# linesensor.net
KiCad netlist of a schematic drawn in EAGLE
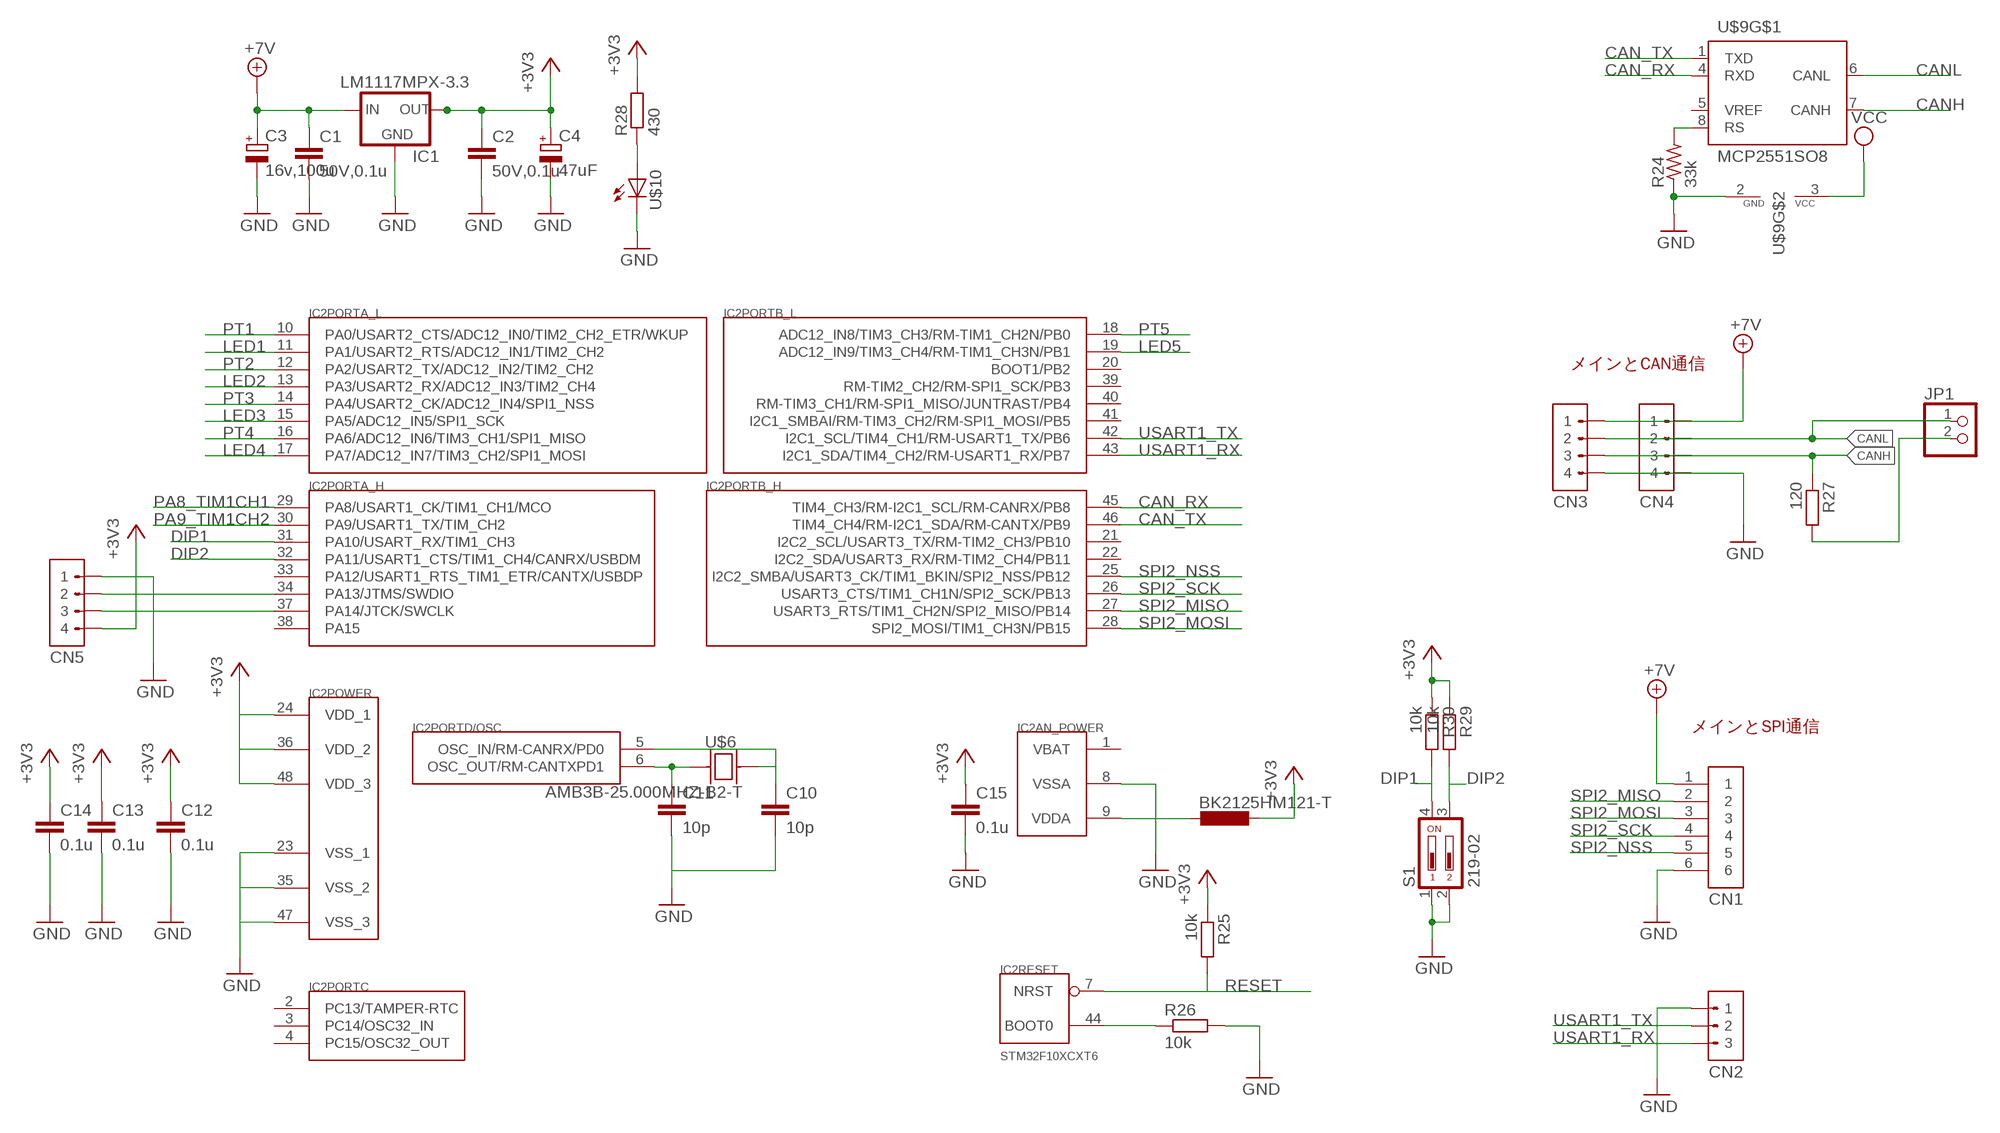
[diagram p0: schematic, sheet 1, part 1 of 2]
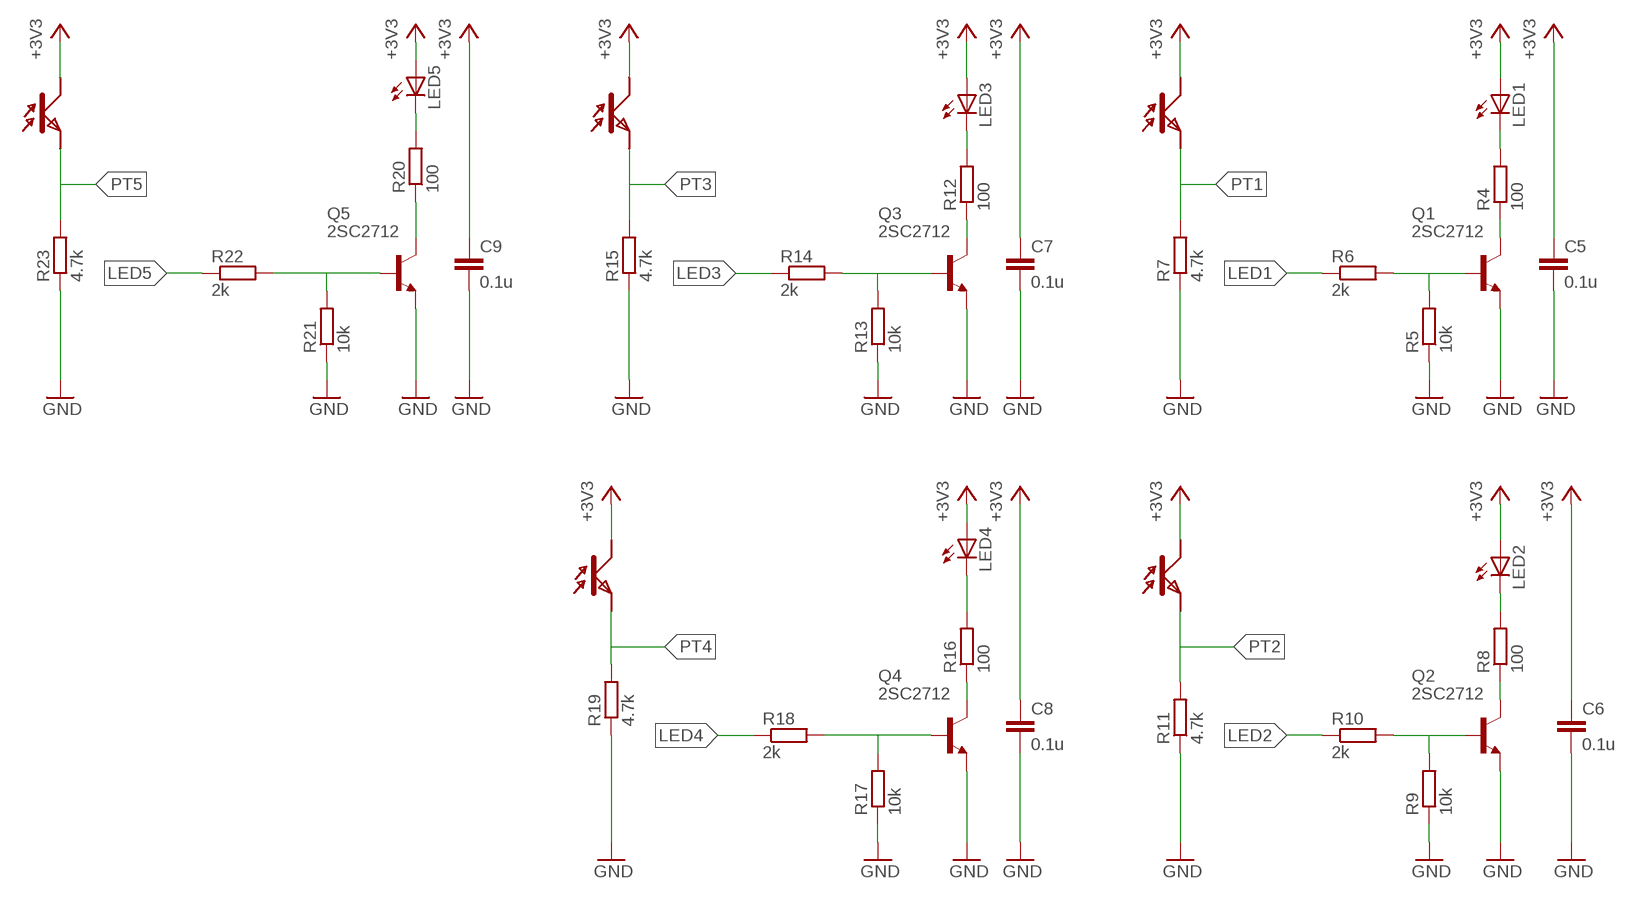
[diagram p1: schematic, sheet 1, part 2 of 2]

(export (version "E")
  (design (tool "Eeschema 10.0.6"))
  (components
    (comp (ref "BK2125HM121-T")
      (value "L-EUL2012C")
      (footprint "eagle-import:L2012C")
      (libsource (lib "eagle-import") (part "L-EUL2012C"))
    )
    (comp (ref "C1")
      (value "50V,0.1u")
      (footprint "eagle-import:C0603K")
      (libsource (lib "eagle-import") (part "C-EUC0603K"))
    )
    (comp (ref "C2")
      (value "50V,0.1u")
      (footprint "eagle-import:C0603K")
      (libsource (lib "eagle-import") (part "C-EUC0603K"))
    )
    (comp (ref "C3")
      (value "16v,100u")
      (footprint "eagle-import:153CLV-0605")
      (libsource (lib "eagle-import") (part "CPOL-EU153CLV-0605"))
    )
    (comp (ref "C4")
      (value "47uF")
      (footprint "eagle-import:153CLV-0405")
      (libsource (lib "eagle-import") (part "CPOL-EU153CLV-0405"))
    )
    (comp (ref "C5")
      (value "0.1u")
      (footprint "eagle-import:C0603K")
      (libsource (lib "eagle-import") (part "C-EUC0603K"))
    )
    (comp (ref "C6")
      (value "0.1u")
      (footprint "eagle-import:C0603K")
      (libsource (lib "eagle-import") (part "C-EUC0603K"))
    )
    (comp (ref "C7")
      (value "0.1u")
      (footprint "eagle-import:C0603K")
      (libsource (lib "eagle-import") (part "C-EUC0603K"))
    )
    (comp (ref "C8")
      (value "0.1u")
      (footprint "eagle-import:C0603K")
      (libsource (lib "eagle-import") (part "C-EUC0603K"))
    )
    (comp (ref "C9")
      (value "0.1u")
      (footprint "eagle-import:C0603K")
      (libsource (lib "eagle-import") (part "C-EUC0603K"))
    )
    (comp (ref "C10")
      (value "10p")
      (footprint "eagle-import:C0603K")
      (libsource (lib "eagle-import") (part "C-EUC0603K"))
    )
    (comp (ref "C11")
      (value "10p")
      (footprint "eagle-import:C0603K")
      (libsource (lib "eagle-import") (part "C-EUC0603K"))
    )
    (comp (ref "C12")
      (value "0.1u")
      (footprint "eagle-import:C0603K")
      (libsource (lib "eagle-import") (part "C-EUC0603K"))
    )
    (comp (ref "C13")
      (value "0.1u")
      (footprint "eagle-import:C0603K")
      (libsource (lib "eagle-import") (part "C-EUC0603K"))
    )
    (comp (ref "C14")
      (value "0.1u")
      (footprint "eagle-import:C0603K")
      (libsource (lib "eagle-import") (part "C-EUC0603K"))
    )
    (comp (ref "C15")
      (value "0.1u")
      (footprint "eagle-import:C0603K")
      (libsource (lib "eagle-import") (part "C-EUC0603K"))
    )
    (comp (ref "CN1")
      (value "CN6")
      (footprint "eagle-import:JST-B6B-XH-A")
      (libsource (lib "eagle-import") (part "CN6"))
    )
    (comp (ref "CN2")
      (value "TOP_TYPE_3PIN")
      (footprint "eagle-import:TOP_TYPE_3PIN")
      (libsource (lib "eagle-import") (part "TOP_TYPE_3PIN"))
    )
    (comp (ref "CN3")
      (value "CN4-JST-XH-TOP")
      (footprint "eagle-import:JST-B4B-XH-A")
      (libsource (lib "eagle-import") (part "CN4-JST-XH-TOP"))
    )
    (comp (ref "CN4")
      (value "CN4-JST-XH-TOP")
      (footprint "eagle-import:JST-B4B-XH-A")
      (libsource (lib "eagle-import") (part "CN4-JST-XH-TOP"))
    )
    (comp (ref "CN5")
      (value "TOP_TYPE_4PIN")
      (footprint "eagle-import:TOP_TYPE_4PIN")
      (libsource (lib "eagle-import") (part "TOP_TYPE_4PIN"))
    )
    (comp (ref "IC1")
      (value "LM1117MPX-3.3")
      (footprint "eagle-import:SOT223")
      (libsource (lib "eagle-import") (part "LM1117"))
    )
    (comp (ref "IC2")
      (value "STM32F10XCXT6")
      (footprint "eagle-import:TQFP48")
      (libsource (lib "eagle-import") (part "STM32F10XCXT6"))
    )
    (comp (ref "JP1")
      (value "PINHD-1X2")
      (footprint "eagle-import:1X02")
      (libsource (lib "eagle-import") (part "PINHD-1X2"))
    )
    (comp (ref "LED1")
      (value "LED3MM")
      (footprint "eagle-import:LED3MM")
      (libsource (lib "eagle-import") (part "LED3MM"))
    )
    (comp (ref "LED2")
      (value "LED3MM")
      (footprint "eagle-import:LED3MM")
      (libsource (lib "eagle-import") (part "LED3MM"))
    )
    (comp (ref "LED3")
      (value "LED3MM")
      (footprint "eagle-import:LED3MM")
      (libsource (lib "eagle-import") (part "LED3MM"))
    )
    (comp (ref "LED4")
      (value "LED3MM")
      (footprint "eagle-import:LED3MM")
      (libsource (lib "eagle-import") (part "LED3MM"))
    )
    (comp (ref "LED5")
      (value "LED3MM")
      (footprint "eagle-import:LED3MM")
      (libsource (lib "eagle-import") (part "LED3MM"))
    )
    (comp (ref "Q1")
      (value "2SC2712")
      (footprint "eagle-import:SC-59(TYPE1)")
      (libsource (lib "eagle-import") (part "2SC2712"))
    )
    (comp (ref "Q2")
      (value "2SC2712")
      (footprint "eagle-import:SC-59(TYPE1)")
      (libsource (lib "eagle-import") (part "2SC2712"))
    )
    (comp (ref "Q3")
      (value "2SC2712")
      (footprint "eagle-import:SC-59(TYPE1)")
      (libsource (lib "eagle-import") (part "2SC2712"))
    )
    (comp (ref "Q4")
      (value "2SC2712")
      (footprint "eagle-import:SC-59(TYPE1)")
      (libsource (lib "eagle-import") (part "2SC2712"))
    )
    (comp (ref "Q5")
      (value "2SC2712")
      (footprint "eagle-import:SC-59(TYPE1)")
      (libsource (lib "eagle-import") (part "2SC2712"))
    )
    (comp (ref "R4")
      (value "100")
      (footprint "eagle-import:R0603")
      (libsource (lib "eagle-import") (part "R-EU_R0603"))
    )
    (comp (ref "R5")
      (value "10k")
      (footprint "eagle-import:R0603")
      (libsource (lib "eagle-import") (part "R-EU_R0603"))
    )
    (comp (ref "R6")
      (value "2k")
      (footprint "eagle-import:R0603")
      (libsource (lib "eagle-import") (part "R-EU_R0603"))
    )
    (comp (ref "R7")
      (value "4.7k")
      (footprint "eagle-import:R0603")
      (libsource (lib "eagle-import") (part "R-EU_R0603"))
    )
    (comp (ref "R8")
      (value "100")
      (footprint "eagle-import:R0603")
      (libsource (lib "eagle-import") (part "R-EU_R0603"))
    )
    (comp (ref "R9")
      (value "10k")
      (footprint "eagle-import:R0603")
      (libsource (lib "eagle-import") (part "R-EU_R0603"))
    )
    (comp (ref "R10")
      (value "2k")
      (footprint "eagle-import:R0603")
      (libsource (lib "eagle-import") (part "R-EU_R0603"))
    )
    (comp (ref "R11")
      (value "4.7k")
      (footprint "eagle-import:R0603")
      (libsource (lib "eagle-import") (part "R-EU_R0603"))
    )
    (comp (ref "R12")
      (value "100")
      (footprint "eagle-import:R0603")
      (libsource (lib "eagle-import") (part "R-EU_R0603"))
    )
    (comp (ref "R13")
      (value "10k")
      (footprint "eagle-import:R0603")
      (libsource (lib "eagle-import") (part "R-EU_R0603"))
    )
    (comp (ref "R14")
      (value "2k")
      (footprint "eagle-import:R0603")
      (libsource (lib "eagle-import") (part "R-EU_R0603"))
    )
    (comp (ref "R15")
      (value "4.7k")
      (footprint "eagle-import:R0603")
      (libsource (lib "eagle-import") (part "R-EU_R0603"))
    )
    (comp (ref "R16")
      (value "100")
      (footprint "eagle-import:R0603")
      (libsource (lib "eagle-import") (part "R-EU_R0603"))
    )
    (comp (ref "R17")
      (value "10k")
      (footprint "eagle-import:R0603")
      (libsource (lib "eagle-import") (part "R-EU_R0603"))
    )
    (comp (ref "R18")
      (value "2k")
      (footprint "eagle-import:R0603")
      (libsource (lib "eagle-import") (part "R-EU_R0603"))
    )
    (comp (ref "R19")
      (value "4.7k")
      (footprint "eagle-import:R0603")
      (libsource (lib "eagle-import") (part "R-EU_R0603"))
    )
    (comp (ref "R20")
      (value "100")
      (footprint "eagle-import:R0603")
      (libsource (lib "eagle-import") (part "R-EU_R0603"))
    )
    (comp (ref "R21")
      (value "10k")
      (footprint "eagle-import:R0603")
      (libsource (lib "eagle-import") (part "R-EU_R0603"))
    )
    (comp (ref "R22")
      (value "2k")
      (footprint "eagle-import:R0603")
      (libsource (lib "eagle-import") (part "R-EU_R0603"))
    )
    (comp (ref "R23")
      (value "4.7k")
      (footprint "eagle-import:R0603")
      (libsource (lib "eagle-import") (part "R-EU_R0603"))
    )
    (comp (ref "R24")
      (value "33k")
      (footprint "eagle-import:R0603")
      (libsource (lib "eagle-import") (part "R-US_R0603"))
    )
    (comp (ref "R25")
      (value "10k")
      (footprint "eagle-import:R0603")
      (libsource (lib "eagle-import") (part "R-EU_R0603"))
    )
    (comp (ref "R26")
      (value "10k")
      (footprint "eagle-import:R0603")
      (libsource (lib "eagle-import") (part "R-EU_R0603"))
    )
    (comp (ref "R27")
      (value "120")
      (footprint "eagle-import:R0603")
      (libsource (lib "eagle-import") (part "R-EU_R0603"))
    )
    (comp (ref "R28")
      (value "430")
      (footprint "eagle-import:R0603")
      (libsource (lib "eagle-import") (part "R-EU_R0603"))
    )
    (comp (ref "R29")
      (value "10k")
      (footprint "eagle-import:R0603")
      (libsource (lib "eagle-import") (part "R-EU_R0603"))
    )
    (comp (ref "R30")
      (value "10k")
      (footprint "eagle-import:R0603")
      (libsource (lib "eagle-import") (part "R-EU_R0603"))
    )
    (comp (ref "S1")
      (value "219-02")
      (footprint "eagle-import:CTS-219-02")
      (libsource (lib "eagle-import") (part "219-02"))
    )
    (comp (ref "U$1")
      (value "SFH213")
      (footprint "eagle-import:SFH213")
      (libsource (lib "eagle-import") (part "SFH213"))
    )
    (comp (ref "U$2")
      (value "SFH213")
      (footprint "eagle-import:SFH213")
      (libsource (lib "eagle-import") (part "SFH213"))
    )
    (comp (ref "U$3")
      (value "SFH213")
      (footprint "eagle-import:SFH213")
      (libsource (lib "eagle-import") (part "SFH213"))
    )
    (comp (ref "U$4")
      (value "SFH213")
      (footprint "eagle-import:SFH213")
      (libsource (lib "eagle-import") (part "SFH213"))
    )
    (comp (ref "U$5")
      (value "SFH213")
      (footprint "eagle-import:SFH213")
      (libsource (lib "eagle-import") (part "SFH213"))
    )
    (comp (ref "U$6")
      (value "AMB3B-25.000MHZ-B2-T")
      (footprint "eagle-import:4LCC")
      (libsource (lib "eagle-import") (part "AMB3B-25.000MHZ-B2-T"))
    )
    (comp (ref "U$9")
      (value "MCP2551SO8")
      (footprint "eagle-import:SO08")
      (libsource (lib "eagle-import") (part "MCP2551SO8"))
    )
    (comp (ref "U$10")
      (value "0603")
      (footprint "eagle-import:0603")
      (libsource (lib "eagle-import") (part "0603"))
    )
  )
  (nets
    (net (code "1") (name "+3V3") (class "Default")
      (node (ref "BK2125HM121-T") (pin "1") (pinfunction "1_1") (pintype "passive"))
      (node (ref "C12") (pin "1") (pinfunction "1_1") (pintype "passive"))
      (node (ref "C13") (pin "1") (pinfunction "1_1") (pintype "passive"))
      (node (ref "C14") (pin "1") (pinfunction "1_1") (pintype "passive"))
      (node (ref "C15") (pin "1") (pinfunction "1_1") (pintype "passive"))
      (node (ref "C2") (pin "1") (pinfunction "1_1") (pintype "passive"))
      (node (ref "C4") (pin "+") (pinfunction "+_+") (pintype "passive"))
      (node (ref "C5") (pin "1") (pinfunction "1_1") (pintype "passive"))
      (node (ref "C6") (pin "1") (pinfunction "1_1") (pintype "passive"))
      (node (ref "C7") (pin "1") (pinfunction "1_1") (pintype "passive"))
      (node (ref "C8") (pin "1") (pinfunction "1_1") (pintype "passive"))
      (node (ref "C9") (pin "1") (pinfunction "1_1") (pintype "passive"))
      (node (ref "CN5") (pin "4") (pinfunction "4_4") (pintype "passive"))
      (node (ref "IC1") (pin "2") (pinfunction "OUT1_2") (pintype "passive"))
      (node (ref "IC1") (pin "4") (pinfunction "OUT_4") (pintype "passive"))
      (node (ref "IC2") (pin "24") (pinfunction "VDD_1_24") (pintype "power_in"))
      (node (ref "IC2") (pin "36") (pinfunction "VDD_2_36") (pintype "power_in"))
      (node (ref "IC2") (pin "48") (pinfunction "VDD_3_48") (pintype "power_in"))
      (node (ref "LED1") (pin "A") (pinfunction "A_A") (pintype "passive"))
      (node (ref "LED2") (pin "A") (pinfunction "A_A") (pintype "passive"))
      (node (ref "LED3") (pin "A") (pinfunction "A_A") (pintype "passive"))
      (node (ref "LED4") (pin "A") (pinfunction "A_A") (pintype "passive"))
      (node (ref "LED5") (pin "A") (pinfunction "A_A") (pintype "passive"))
      (node (ref "R25") (pin "1") (pinfunction "1_1") (pintype "passive"))
      (node (ref "R28") (pin "2") (pinfunction "2_2") (pintype "passive"))
      (node (ref "R29") (pin "1") (pinfunction "1_1") (pintype "passive"))
      (node (ref "R30") (pin "1") (pinfunction "1_1") (pintype "passive"))
      (node (ref "U$1") (pin "P$1") (pinfunction "P$1_P$1") (pintype "bidirectional"))
      (node (ref "U$2") (pin "P$1") (pinfunction "P$1_P$1") (pintype "bidirectional"))
      (node (ref "U$3") (pin "P$1") (pinfunction "P$1_P$1") (pintype "bidirectional"))
      (node (ref "U$4") (pin "P$1") (pinfunction "P$1_P$1") (pintype "bidirectional"))
      (node (ref "U$5") (pin "P$1") (pinfunction "P$1_P$1") (pintype "bidirectional"))
    )
    (net (code "2") (name "+7V") (class "Default")
      (node (ref "C1") (pin "1") (pinfunction "1_1") (pintype "passive"))
      (node (ref "C3") (pin "+") (pinfunction "+_+") (pintype "passive"))
      (node (ref "CN1") (pin "1") (pinfunction "1_1") (pintype "passive"))
      (node (ref "CN3") (pin "1") (pinfunction "1_1") (pintype "passive"))
      (node (ref "CN4") (pin "1") (pinfunction "1_1") (pintype "passive"))
      (node (ref "IC1") (pin "3") (pinfunction "IN_3") (pintype "input"))
    )
    (net (code "3") (name "/CAN_RX") (class "Default")
      (node (ref "IC2") (pin "45") (pinfunction "TIM4_CH3/RM-I2C1_SCL/RM-CANRX/PB8_45") (pintype "bidirectional"))
      (node (ref "U$9") (pin "4") (pinfunction "RXD_4") (pintype "bidirectional"))
    )
    (net (code "4") (name "/CAN_TX") (class "Default")
      (node (ref "IC2") (pin "46") (pinfunction "TIM4_CH4/RM-I2C1_SDA/RM-CANTX/PB9_46") (pintype "bidirectional"))
      (node (ref "U$9") (pin "1") (pinfunction "TXD_1") (pintype "bidirectional"))
    )
    (net (code "5") (name "/DIP1") (class "Default")
      (node (ref "IC2") (pin "31") (pinfunction "PA10/USART_RX/TIM1_CH3_31") (pintype "bidirectional"))
      (node (ref "R30") (pin "2") (pinfunction "2_2") (pintype "passive"))
      (node (ref "S1") (pin "4") (pinfunction "4_4") (pintype "passive"))
    )
    (net (code "6") (name "/DIP2") (class "Default")
      (node (ref "IC2") (pin "32") (pinfunction "PA11/USART1_CTS/TIM1_CH4/CANRX/USBDM_32") (pintype "bidirectional"))
      (node (ref "R29") (pin "2") (pinfunction "2_2") (pintype "passive"))
      (node (ref "S1") (pin "3") (pinfunction "3_3") (pintype "passive"))
    )
    (net (code "7") (name "/PA8_TIM1CH1") (class "Default")
      (node (ref "IC2") (pin "29") (pinfunction "PA8/USART1_CK/TIM1_CH1/MCO_29") (pintype "bidirectional"))
    )
    (net (code "8") (name "/PA9_TIM1CH2") (class "Default")
      (node (ref "IC2") (pin "30") (pinfunction "PA9/USART1_TX/TIM_CH2_30") (pintype "bidirectional"))
    )
    (net (code "9") (name "/RESET") (class "Default")
      (node (ref "IC2") (pin "7") (pinfunction "NRST_7") (pintype "input"))
      (node (ref "R25") (pin "2") (pinfunction "2_2") (pintype "passive"))
    )
    (net (code "10") (name "/SPI2_MISO") (class "Default")
      (node (ref "CN1") (pin "2") (pinfunction "2_2") (pintype "passive"))
      (node (ref "IC2") (pin "27") (pinfunction "USART3_RTS/TIM1_CH2N/SPI2_MISO/PB14_27") (pintype "bidirectional"))
    )
    (net (code "11") (name "/SPI2_MOSI") (class "Default")
      (node (ref "CN1") (pin "3") (pinfunction "3_3") (pintype "passive"))
      (node (ref "IC2") (pin "28") (pinfunction "SPI2_MOSI/TIM1_CH3N/PB15_28") (pintype "bidirectional"))
    )
    (net (code "12") (name "/SPI2_NSS") (class "Default")
      (node (ref "CN1") (pin "5") (pinfunction "5_5") (pintype "passive"))
      (node (ref "IC2") (pin "25") (pinfunction "I2C2_SMBA/USART3_CK/TIM1_BKIN/SPI2_NSS/PB12_25") (pintype "bidirectional"))
    )
    (net (code "13") (name "/SPI2_SCK") (class "Default")
      (node (ref "CN1") (pin "4") (pinfunction "4_4") (pintype "passive"))
      (node (ref "IC2") (pin "26") (pinfunction "USART3_CTS/TIM1_CH1N/SPI2_SCK/PB13_26") (pintype "bidirectional"))
    )
    (net (code "14") (name "/USART1_RX") (class "Default")
      (node (ref "CN2") (pin "3") (pinfunction "3_3") (pintype "passive"))
      (node (ref "IC2") (pin "43") (pinfunction "I2C1_SDA/TIM4_CH2/RM-USART1_RX/PB7_43") (pintype "bidirectional"))
    )
    (net (code "15") (name "/USART1_TX") (class "Default")
      (node (ref "CN2") (pin "2") (pinfunction "2_2") (pintype "passive"))
      (node (ref "IC2") (pin "42") (pinfunction "I2C1_SCL/TIM4_CH1/RM-USART1_TX/PB6_42") (pintype "bidirectional"))
    )
    (net (code "16") (name "/VBAT") (class "Default")
      (node (ref "IC2") (pin "1") (pinfunction "VBAT_1") (pintype "power_in"))
    )
    (net (code "17") (name "CANH") (class "Default")
      (node (ref "CN3") (pin "3") (pinfunction "3_3") (pintype "passive"))
      (node (ref "CN4") (pin "3") (pinfunction "3_3") (pintype "passive"))
      (node (ref "R27") (pin "1") (pinfunction "1_1") (pintype "passive"))
      (node (ref "U$9") (pin "7") (pinfunction "CANH_7") (pintype "bidirectional"))
    )
    (net (code "18") (name "CANL") (class "Default")
      (node (ref "CN3") (pin "2") (pinfunction "2_2") (pintype "passive"))
      (node (ref "CN4") (pin "2") (pinfunction "2_2") (pintype "passive"))
      (node (ref "JP1") (pin "1") (pinfunction "1_1") (pintype "passive"))
      (node (ref "U$9") (pin "6") (pinfunction "CANL_6") (pintype "bidirectional"))
    )
    (net (code "19") (name "GND") (class "Default")
      (node (ref "C1") (pin "2") (pinfunction "2_2") (pintype "passive"))
      (node (ref "C10") (pin "2") (pinfunction "2_2") (pintype "passive"))
      (node (ref "C11") (pin "2") (pinfunction "2_2") (pintype "passive"))
      (node (ref "C12") (pin "2") (pinfunction "2_2") (pintype "passive"))
      (node (ref "C13") (pin "2") (pinfunction "2_2") (pintype "passive"))
      (node (ref "C14") (pin "2") (pinfunction "2_2") (pintype "passive"))
      (node (ref "C15") (pin "2") (pinfunction "2_2") (pintype "passive"))
      (node (ref "C2") (pin "2") (pinfunction "2_2") (pintype "passive"))
      (node (ref "C3") (pin "-") (pinfunction "-_-") (pintype "passive"))
      (node (ref "C4") (pin "-") (pinfunction "-_-") (pintype "passive"))
      (node (ref "C5") (pin "2") (pinfunction "2_2") (pintype "passive"))
      (node (ref "C6") (pin "2") (pinfunction "2_2") (pintype "passive"))
      (node (ref "C7") (pin "2") (pinfunction "2_2") (pintype "passive"))
      (node (ref "C8") (pin "2") (pinfunction "2_2") (pintype "passive"))
      (node (ref "C9") (pin "2") (pinfunction "2_2") (pintype "passive"))
      (node (ref "CN1") (pin "6") (pinfunction "6_6") (pintype "passive"))
      (node (ref "CN2") (pin "1") (pinfunction "1_1") (pintype "passive"))
      (node (ref "CN3") (pin "4") (pinfunction "4_4") (pintype "passive"))
      (node (ref "CN4") (pin "4") (pinfunction "4_4") (pintype "passive"))
      (node (ref "CN5") (pin "1") (pinfunction "1_1") (pintype "passive"))
      (node (ref "IC1") (pin "1") (pinfunction "GND_1") (pintype "input"))
      (node (ref "IC2") (pin "23") (pinfunction "VSS_1_23") (pintype "power_in"))
      (node (ref "IC2") (pin "35") (pinfunction "VSS_2_35") (pintype "power_in"))
      (node (ref "IC2") (pin "47") (pinfunction "VSS_3_47") (pintype "power_in"))
      (node (ref "IC2") (pin "8") (pinfunction "VSSA_8") (pintype "power_in"))
      (node (ref "Q1") (pin "E") (pinfunction "E_E") (pintype "passive"))
      (node (ref "Q2") (pin "E") (pinfunction "E_E") (pintype "passive"))
      (node (ref "Q3") (pin "E") (pinfunction "E_E") (pintype "passive"))
      (node (ref "Q4") (pin "E") (pinfunction "E_E") (pintype "passive"))
      (node (ref "Q5") (pin "E") (pinfunction "E_E") (pintype "passive"))
      (node (ref "R11") (pin "1") (pinfunction "1_1") (pintype "passive"))
      (node (ref "R13") (pin "1") (pinfunction "1_1") (pintype "passive"))
      (node (ref "R15") (pin "1") (pinfunction "1_1") (pintype "passive"))
      (node (ref "R17") (pin "1") (pinfunction "1_1") (pintype "passive"))
      (node (ref "R19") (pin "1") (pinfunction "1_1") (pintype "passive"))
      (node (ref "R21") (pin "1") (pinfunction "1_1") (pintype "passive"))
      (node (ref "R23") (pin "1") (pinfunction "1_1") (pintype "passive"))
      (node (ref "R24") (pin "1") (pinfunction "1_1") (pintype "passive"))
      (node (ref "R26") (pin "2") (pinfunction "2_2") (pintype "passive"))
      (node (ref "R5") (pin "1") (pinfunction "1_1") (pintype "passive"))
      (node (ref "R7") (pin "1") (pinfunction "1_1") (pintype "passive"))
      (node (ref "R9") (pin "1") (pinfunction "1_1") (pintype "passive"))
      (node (ref "S1") (pin "1") (pinfunction "1_1") (pintype "passive"))
      (node (ref "S1") (pin "2") (pinfunction "2_2") (pintype "passive"))
      (node (ref "U$10") (pin "C") (pinfunction "C_C") (pintype "passive"))
      (node (ref "U$9") (pin "2") (pinfunction "GND_2") (pintype "power_in"))
    )
    (net (code "20") (name "LED1") (class "Default")
      (node (ref "IC2") (pin "11") (pinfunction "PA1/USART2_RTS/ADC12_IN1/TIM2_CH2_11") (pintype "bidirectional"))
      (node (ref "R6") (pin "1") (pinfunction "1_1") (pintype "passive"))
    )
    (net (code "21") (name "LED2") (class "Default")
      (node (ref "IC2") (pin "13") (pinfunction "PA3/USART2_RX/ADC12_IN3/TIM2_CH4_13") (pintype "bidirectional"))
      (node (ref "R10") (pin "1") (pinfunction "1_1") (pintype "passive"))
    )
    (net (code "22") (name "LED3") (class "Default")
      (node (ref "IC2") (pin "15") (pinfunction "PA5/ADC12_IN5/SPI1_SCK_15") (pintype "bidirectional"))
      (node (ref "R14") (pin "1") (pinfunction "1_1") (pintype "passive"))
    )
    (net (code "23") (name "LED4") (class "Default")
      (node (ref "IC2") (pin "17") (pinfunction "PA7/ADC12_IN7/TIM3_CH2/SPI1_MOSI_17") (pintype "bidirectional"))
      (node (ref "R18") (pin "1") (pinfunction "1_1") (pintype "passive"))
    )
    (net (code "24") (name "LED5") (class "Default")
      (node (ref "IC2") (pin "19") (pinfunction "ADC12_IN9/TIM3_CH4/RM-TIM1_CH3N/PB1_19") (pintype "bidirectional"))
      (node (ref "R22") (pin "1") (pinfunction "1_1") (pintype "passive"))
    )
    (net (code "25") (name "Net-(IC2A-VDDA)") (class "Default")
      (node (ref "BK2125HM121-T") (pin "2") (pinfunction "2_2") (pintype "passive"))
      (node (ref "IC2") (pin "9") (pinfunction "VDDA_9") (pintype "power_in"))
    )
    (net (code "26") (name "Net-(IC2B-PA13{slash}JTMS{slash}SWDIO)") (class "Default")
      (node (ref "CN5") (pin "2") (pinfunction "2_2") (pintype "passive"))
      (node (ref "IC2") (pin "34") (pinfunction "PA13/JTMS/SWDIO_34") (pintype "bidirectional"))
    )
    (net (code "27") (name "Net-(IC2B-PA14{slash}JTCK{slash}SWCLK)") (class "Default")
      (node (ref "CN5") (pin "3") (pinfunction "3_3") (pintype "passive"))
      (node (ref "IC2") (pin "37") (pinfunction "PA14/JTCK/SWCLK_37") (pintype "bidirectional"))
    )
    (net (code "28") (name "Net-(IC2G-OSC_IN{slash}RM-CANRX{slash}PD0)") (class "Default")
      (node (ref "C10") (pin "1") (pinfunction "1_1") (pintype "passive"))
      (node (ref "IC2") (pin "5") (pinfunction "OSC_IN/RM-CANRX/PD0_5") (pintype "bidirectional"))
      (node (ref "U$6") (pin "3") (pinfunction "P$2_3") (pintype "bidirectional"))
    )
    (net (code "29") (name "Net-(IC2G-OSC_OUT{slash}RM-CANTXPD1)") (class "Default")
      (node (ref "C11") (pin "1") (pinfunction "1_1") (pintype "passive"))
      (node (ref "IC2") (pin "6") (pinfunction "OSC_OUT/RM-CANTXPD1_6") (pintype "bidirectional"))
      (node (ref "U$6") (pin "1") (pinfunction "P$1_1") (pintype "bidirectional"))
    )
    (net (code "30") (name "Net-(IC2I-BOOT0)") (class "Default")
      (node (ref "IC2") (pin "44") (pinfunction "BOOT0_44") (pintype "input"))
      (node (ref "R26") (pin "1") (pinfunction "1_1") (pintype "passive"))
    )
    (net (code "31") (name "Net-(JP1-Pad2)") (class "Default")
      (node (ref "JP1") (pin "2") (pinfunction "2_2") (pintype "passive"))
      (node (ref "R27") (pin "2") (pinfunction "2_2") (pintype "passive"))
    )
    (net (code "32") (name "Net-(LED1-C)") (class "Default")
      (node (ref "LED1") (pin "K") (pinfunction "C_K") (pintype "passive"))
      (node (ref "R4") (pin "2") (pinfunction "2_2") (pintype "passive"))
    )
    (net (code "33") (name "Net-(LED2-C)") (class "Default")
      (node (ref "LED2") (pin "K") (pinfunction "C_K") (pintype "passive"))
      (node (ref "R8") (pin "2") (pinfunction "2_2") (pintype "passive"))
    )
    (net (code "34") (name "Net-(LED3-C)") (class "Default")
      (node (ref "LED3") (pin "K") (pinfunction "C_K") (pintype "passive"))
      (node (ref "R12") (pin "2") (pinfunction "2_2") (pintype "passive"))
    )
    (net (code "35") (name "Net-(LED4-C)") (class "Default")
      (node (ref "LED4") (pin "K") (pinfunction "C_K") (pintype "passive"))
      (node (ref "R16") (pin "2") (pinfunction "2_2") (pintype "passive"))
    )
    (net (code "36") (name "Net-(LED5-C)") (class "Default")
      (node (ref "LED5") (pin "K") (pinfunction "C_K") (pintype "passive"))
      (node (ref "R20") (pin "2") (pinfunction "2_2") (pintype "passive"))
    )
    (net (code "37") (name "Net-(Q1-PadB)") (class "Default")
      (node (ref "Q1") (pin "B") (pinfunction "B_B") (pintype "passive"))
      (node (ref "R5") (pin "2") (pinfunction "2_2") (pintype "passive"))
      (node (ref "R6") (pin "2") (pinfunction "2_2") (pintype "passive"))
    )
    (net (code "38") (name "Net-(Q1-PadC)") (class "Default")
      (node (ref "Q1") (pin "C") (pinfunction "C_C") (pintype "passive"))
      (node (ref "R4") (pin "1") (pinfunction "1_1") (pintype "passive"))
    )
    (net (code "39") (name "Net-(Q2-PadB)") (class "Default")
      (node (ref "Q2") (pin "B") (pinfunction "B_B") (pintype "passive"))
      (node (ref "R10") (pin "2") (pinfunction "2_2") (pintype "passive"))
      (node (ref "R9") (pin "2") (pinfunction "2_2") (pintype "passive"))
    )
    (net (code "40") (name "Net-(Q2-PadC)") (class "Default")
      (node (ref "Q2") (pin "C") (pinfunction "C_C") (pintype "passive"))
      (node (ref "R8") (pin "1") (pinfunction "1_1") (pintype "passive"))
    )
    (net (code "41") (name "Net-(Q3-PadB)") (class "Default")
      (node (ref "Q3") (pin "B") (pinfunction "B_B") (pintype "passive"))
      (node (ref "R13") (pin "2") (pinfunction "2_2") (pintype "passive"))
      (node (ref "R14") (pin "2") (pinfunction "2_2") (pintype "passive"))
    )
    (net (code "42") (name "Net-(Q3-PadC)") (class "Default")
      (node (ref "Q3") (pin "C") (pinfunction "C_C") (pintype "passive"))
      (node (ref "R12") (pin "1") (pinfunction "1_1") (pintype "passive"))
    )
    (net (code "43") (name "Net-(Q4-PadB)") (class "Default")
      (node (ref "Q4") (pin "B") (pinfunction "B_B") (pintype "passive"))
      (node (ref "R17") (pin "2") (pinfunction "2_2") (pintype "passive"))
      (node (ref "R18") (pin "2") (pinfunction "2_2") (pintype "passive"))
    )
    (net (code "44") (name "Net-(Q4-PadC)") (class "Default")
      (node (ref "Q4") (pin "C") (pinfunction "C_C") (pintype "passive"))
      (node (ref "R16") (pin "1") (pinfunction "1_1") (pintype "passive"))
    )
    (net (code "45") (name "Net-(Q5-PadB)") (class "Default")
      (node (ref "Q5") (pin "B") (pinfunction "B_B") (pintype "passive"))
      (node (ref "R21") (pin "2") (pinfunction "2_2") (pintype "passive"))
      (node (ref "R22") (pin "2") (pinfunction "2_2") (pintype "passive"))
    )
    (net (code "46") (name "Net-(Q5-PadC)") (class "Default")
      (node (ref "Q5") (pin "C") (pinfunction "C_C") (pintype "passive"))
      (node (ref "R20") (pin "1") (pinfunction "1_1") (pintype "passive"))
    )
    (net (code "47") (name "Net-(R28-Pad1)") (class "Default")
      (node (ref "R28") (pin "1") (pinfunction "1_1") (pintype "passive"))
      (node (ref "U$10") (pin "A") (pinfunction "A_A") (pintype "passive"))
    )
    (net (code "48") (name "Net-(U$9A-RS)") (class "Default")
      (node (ref "R24") (pin "2") (pinfunction "2_2") (pintype "passive"))
      (node (ref "U$9") (pin "8") (pinfunction "RS_8") (pintype "bidirectional"))
    )
    (net (code "49") (name "PT1") (class "Default")
      (node (ref "IC2") (pin "10") (pinfunction "PA0/USART2_CTS/ADC12_IN0/TIM2_CH2_ETR/WKUP_10") (pintype "bidirectional"))
      (node (ref "R7") (pin "2") (pinfunction "2_2") (pintype "passive"))
      (node (ref "U$1") (pin "P$2") (pinfunction "P$2_P$2") (pintype "bidirectional"))
    )
    (net (code "50") (name "PT2") (class "Default")
      (node (ref "IC2") (pin "12") (pinfunction "PA2/USART2_TX/ADC12_IN2/TIM2_CH2_12") (pintype "bidirectional"))
      (node (ref "R11") (pin "2") (pinfunction "2_2") (pintype "passive"))
      (node (ref "U$2") (pin "P$2") (pinfunction "P$2_P$2") (pintype "bidirectional"))
    )
    (net (code "51") (name "PT3") (class "Default")
      (node (ref "IC2") (pin "14") (pinfunction "PA4/USART2_CK/ADC12_IN4/SPI1_NSS_14") (pintype "bidirectional"))
      (node (ref "R15") (pin "2") (pinfunction "2_2") (pintype "passive"))
      (node (ref "U$3") (pin "P$2") (pinfunction "P$2_P$2") (pintype "bidirectional"))
    )
    (net (code "52") (name "PT4") (class "Default")
      (node (ref "IC2") (pin "16") (pinfunction "PA6/ADC12_IN6/TIM3_CH1/SPI1_MISO_16") (pintype "bidirectional"))
      (node (ref "R19") (pin "2") (pinfunction "2_2") (pintype "passive"))
      (node (ref "U$4") (pin "P$2") (pinfunction "P$2_P$2") (pintype "bidirectional"))
    )
    (net (code "53") (name "PT5") (class "Default")
      (node (ref "IC2") (pin "18") (pinfunction "ADC12_IN8/TIM3_CH3/RM-TIM1_CH2N/PB0_18") (pintype "bidirectional"))
      (node (ref "R23") (pin "2") (pinfunction "2_2") (pintype "passive"))
      (node (ref "U$5") (pin "P$2") (pinfunction "P$2_P$2") (pintype "bidirectional"))
    )
    (net (code "54") (name "VCC") (class "Default")
      (node (ref "U$9") (pin "3") (pinfunction "VCC_3") (pintype "power_in"))
    )
    (net (code "55") (name "unconnected-(IC2B-PA12{slash}USART1_RTS_TIM1_ETR{slash}CANTX{slash}USBDP-Pad33)") (class "Default")
      (node (ref "IC2") (pin "33") (pinfunction "PA12/USART1_RTS_TIM1_ETR/CANTX/USBDP_33") (pintype "bidirectional"))
    )
    (net (code "56") (name "unconnected-(IC2B-PA15-Pad38)") (class "Default")
      (node (ref "IC2") (pin "38") (pinfunction "PA15_38") (pintype "bidirectional"))
    )
    (net (code "57") (name "unconnected-(IC2D-I2C2_SCL{slash}USART3_TX{slash}RM-TIM2_CH3{slash}PB10-Pad21)") (class "Default")
      (node (ref "IC2") (pin "21") (pinfunction "I2C2_SCL/USART3_TX/RM-TIM2_CH3/PB10_21") (pintype "bidirectional"))
    )
    (net (code "58") (name "unconnected-(IC2D-I2C2_SDA{slash}USART3_RX{slash}RM-TIM2_CH4{slash}PB11-Pad22)") (class "Default")
      (node (ref "IC2") (pin "22") (pinfunction "I2C2_SDA/USART3_RX/RM-TIM2_CH4/PB11_22") (pintype "bidirectional"))
    )
    (net (code "59") (name "unconnected-(IC2E-BOOT1{slash}PB2-Pad20)") (class "Default")
      (node (ref "IC2") (pin "20") (pinfunction "BOOT1/PB2_20") (pintype "bidirectional"))
    )
    (net (code "60") (name "unconnected-(IC2E-I2C1_SMBAI{slash}RM-TIM3_CH2{slash}RM-SPI1_MOSI{slash}PB5-Pad41)") (class "Default")
      (node (ref "IC2") (pin "41") (pinfunction "I2C1_SMBAI/RM-TIM3_CH2/RM-SPI1_MOSI/PB5_41") (pintype "bidirectional"))
    )
    (net (code "61") (name "unconnected-(IC2E-RM-TIM2_CH2{slash}RM-SPI1_SCK{slash}PB3-Pad39)") (class "Default")
      (node (ref "IC2") (pin "39") (pinfunction "RM-TIM2_CH2/RM-SPI1_SCK/PB3_39") (pintype "bidirectional"))
    )
    (net (code "62") (name "unconnected-(IC2E-RM-TIM3_CH1{slash}RM-SPI1_MISO{slash}JUNTRAST{slash}PB4-Pad40)") (class "Default")
      (node (ref "IC2") (pin "40") (pinfunction "RM-TIM3_CH1/RM-SPI1_MISO/JUNTRAST/PB4_40") (pintype "bidirectional"))
    )
    (net (code "63") (name "unconnected-(IC2F-PC13{slash}TAMPER-RTC-Pad2)") (class "Default")
      (node (ref "IC2") (pin "2") (pinfunction "PC13/TAMPER-RTC_2") (pintype "bidirectional"))
    )
    (net (code "64") (name "unconnected-(IC2F-PC14{slash}OSC32_IN-Pad3)") (class "Default")
      (node (ref "IC2") (pin "3") (pinfunction "PC14/OSC32_IN_3") (pintype "bidirectional"))
    )
    (net (code "65") (name "unconnected-(IC2F-PC15{slash}OSC32_OUT-Pad4)") (class "Default")
      (node (ref "IC2") (pin "4") (pinfunction "PC15/OSC32_OUT_4") (pintype "bidirectional"))
    )
    (net (code "66") (name "unconnected-(U$9A-VREF-Pad5)") (class "Default")
      (node (ref "U$9") (pin "5") (pinfunction "VREF_5") (pintype "bidirectional"))
    )
  )
)
